# led2ch_v0_2.net
KiCad netlist of a schematic drawn in EAGLE
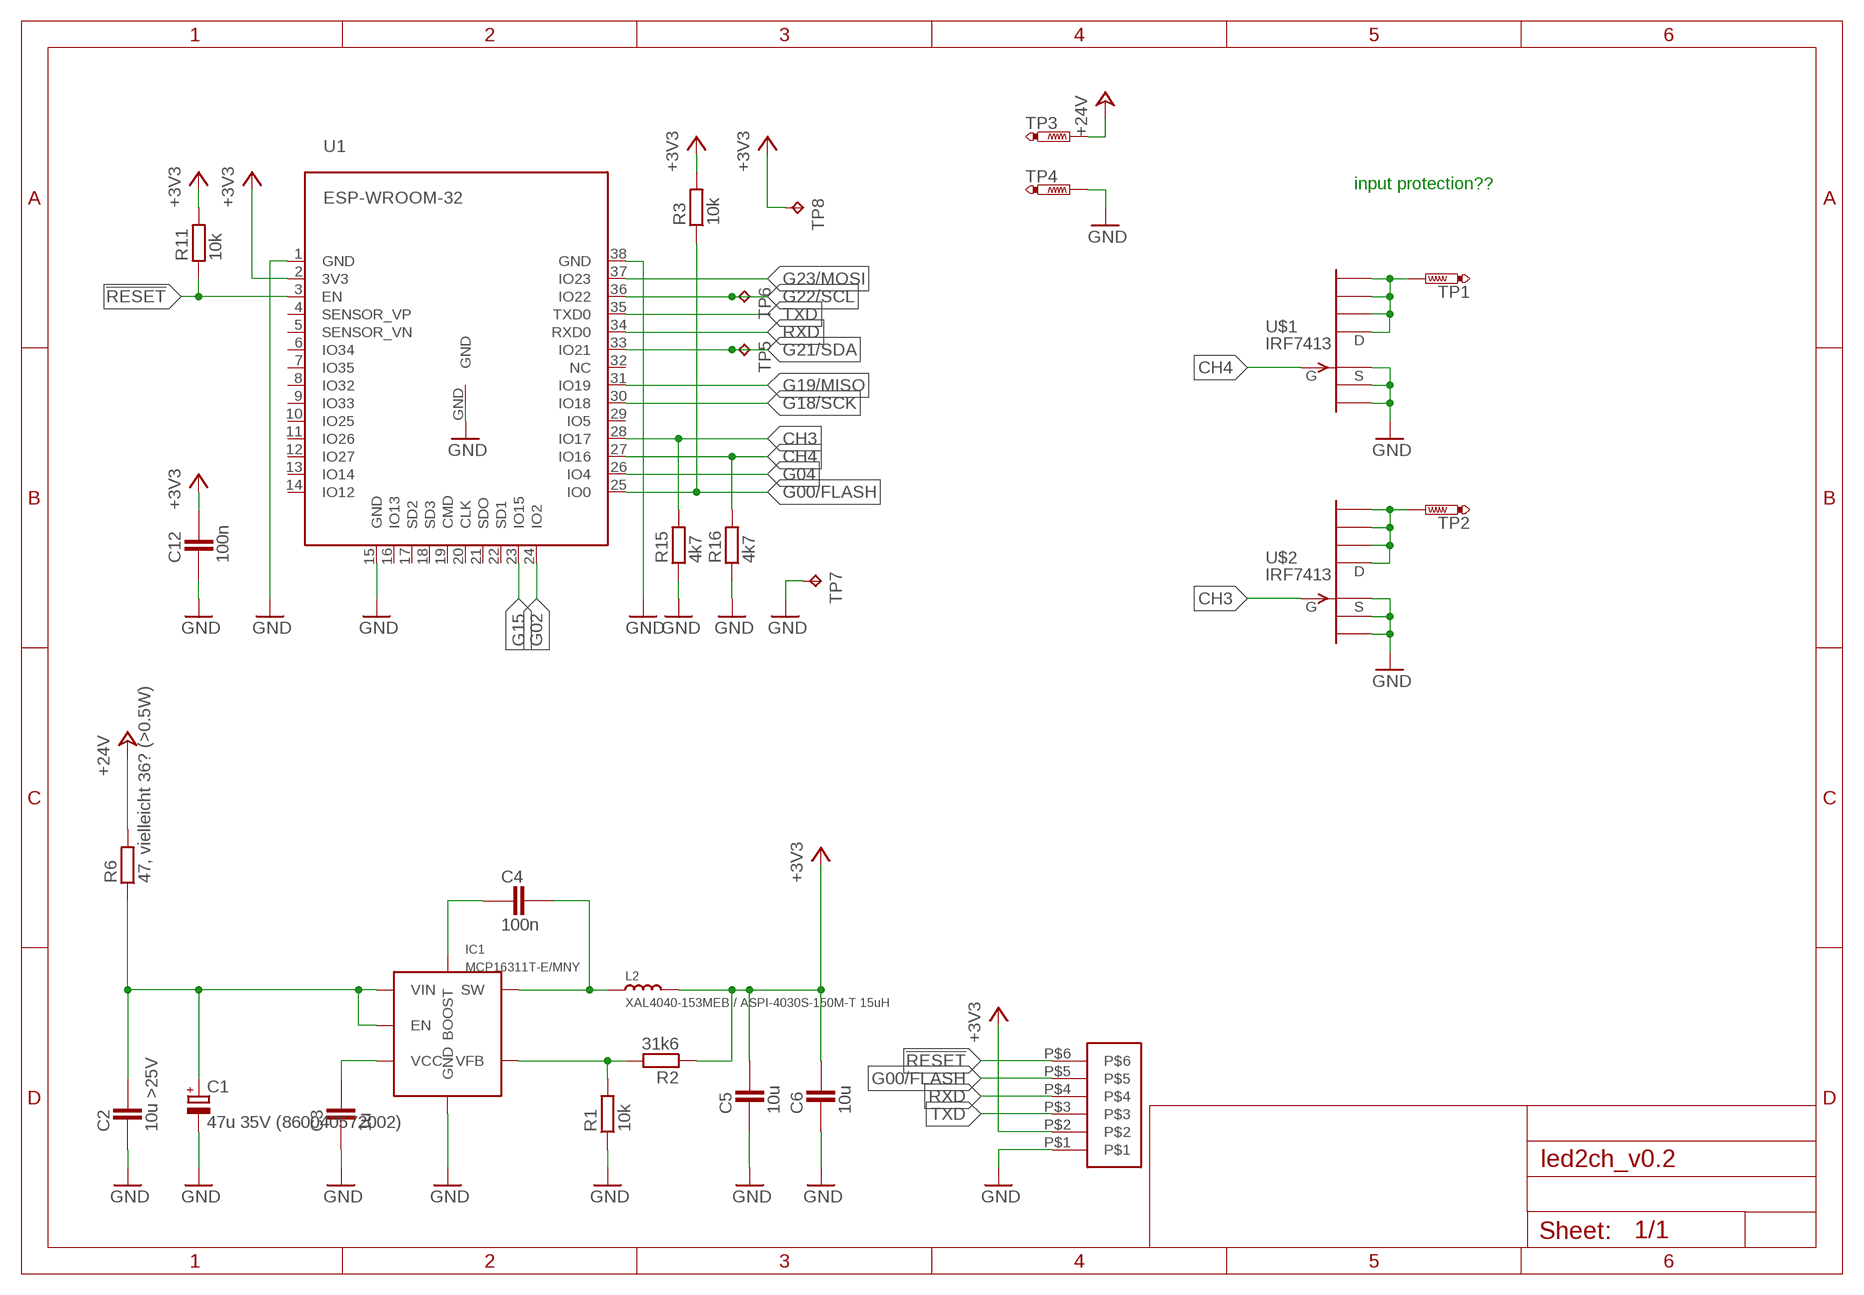
[diagram p0: schematic, sheet 1]

(export (version "E")
  (design (tool "Eeschema 10.0.6"))
  (components
    (comp (ref "C1")
      (value "47u 35V (860040572002)")
      (footprint "eagle-import:E2-5")
      (libsource (lib "eagle-import") (part "CPOL-EUE2-5"))
    )
    (comp (ref "C2")
      (value "10u >25V")
      (footprint "eagle-import:CAPC2012X145AN")
      (libsource (lib "eagle-import") (part "CAPACITOR_0805"))
    )
    (comp (ref "C3")
      (value "1u")
      (footprint "eagle-import:CAPC1608X92N")
      (libsource (lib "eagle-import") (part "CAPACITOR_0603"))
    )
    (comp (ref "C4")
      (value "100n")
      (footprint "eagle-import:CAPC1005X60N")
      (libsource (lib "eagle-import") (part "CAPACITOR_0402"))
    )
    (comp (ref "C5")
      (value "10u")
      (footprint "eagle-import:CAPC2012X145AN")
      (libsource (lib "eagle-import") (part "CAPACITOR_0805"))
    )
    (comp (ref "C6")
      (value "10u")
      (footprint "eagle-import:CAPC2012X145AN")
      (libsource (lib "eagle-import") (part "CAPACITOR_0805"))
    )
    (comp (ref "C12")
      (value "100n")
      (footprint "eagle-import:CAPC1005X60N")
      (libsource (lib "eagle-import") (part "CAPACITOR_0402"))
    )
    (comp (ref "IC1")
      (value "MCP16311T-E/MNY")
      (footprint "eagle-import:TDFN8")
      (libsource (lib "eagle-import") (part "MCP16311-TDFN"))
    )
    (comp (ref "L2")
      (value "XAL4040-153MEB / ASPI-4030S-150M-T 15uH")
      (footprint "eagle-import:L0420")
      (fields (field (name "MPN") "SPD3D16-4R7M"))
      (libsource (lib "eagle-import") (part "SMD-POWER-INDUCTOR-4.7UH-20%-750MA(2P-3.9X3.9MM)"))
    )
    (comp (ref "R1")
      (value "10k")
      (footprint "eagle-import:RESC1005X40AN")
      (libsource (lib "eagle-import") (part "RESISTOR_0402"))
    )
    (comp (ref "R2")
      (value "31k6")
      (footprint "eagle-import:RESC1005X40AN")
      (libsource (lib "eagle-import") (part "RESISTOR_0402"))
    )
    (comp (ref "R3")
      (value "10k")
      (footprint "eagle-import:RESC1005X40AN")
      (libsource (lib "eagle-import") (part "RESISTOR_0402"))
    )
    (comp (ref "R6")
      (value "47, vielleicht 36? (>0.5W)")
      (footprint "eagle-import:RESC3115X70N")
      (libsource (lib "eagle-import") (part "RESISTOR_1206"))
    )
    (comp (ref "R11")
      (value "10k")
      (footprint "eagle-import:RESC1005X40AN")
      (libsource (lib "eagle-import") (part "RESISTOR_0402"))
    )
    (comp (ref "R15")
      (value "4k7")
      (footprint "eagle-import:RESC1005X40AN")
      (libsource (lib "eagle-import") (part "RESISTOR_0402"))
    )
    (comp (ref "R16")
      (value "4k7")
      (footprint "eagle-import:RESC1005X40AN")
      (libsource (lib "eagle-import") (part "RESISTOR_0402"))
    )
    (comp (ref "TP1")
      (value "PTR1B1,27")
      (footprint "eagle-import:B1,27")
      (libsource (lib "eagle-import") (part "PTR1B1,27"))
    )
    (comp (ref "TP2")
      (value "PTR1B1,27")
      (footprint "eagle-import:B1,27")
      (libsource (lib "eagle-import") (part "PTR1B1,27"))
    )
    (comp (ref "TP3")
      (value "PTR1B2,54")
      (footprint "eagle-import:B2,54")
      (libsource (lib "eagle-import") (part "PTR1B2,54"))
    )
    (comp (ref "TP4")
      (value "PTR1B2,54")
      (footprint "eagle-import:B2,54")
      (libsource (lib "eagle-import") (part "PTR1B2,54"))
    )
    (comp (ref "TP5")
      (value "TPB1,27")
      (footprint "eagle-import:B1,27")
      (libsource (lib "eagle-import") (part "TPB1,27"))
    )
    (comp (ref "TP6")
      (value "TPB1,27")
      (footprint "eagle-import:B1,27")
      (libsource (lib "eagle-import") (part "TPB1,27"))
    )
    (comp (ref "TP7")
      (value "TPB1,27")
      (footprint "eagle-import:B1,27")
      (libsource (lib "eagle-import") (part "TPB1,27"))
    )
    (comp (ref "TP8")
      (value "TPB1,27")
      (footprint "eagle-import:B1,27")
      (libsource (lib "eagle-import") (part "TPB1,27"))
    )
    (comp (ref "U$1")
      (value "IRF7413")
      (footprint "eagle-import:SO-8")
      (libsource (lib "eagle-import") (part "IRF7413"))
    )
    (comp (ref "U$2")
      (value "IRF7413")
      (footprint "eagle-import:SO-8")
      (libsource (lib "eagle-import") (part "IRF7413"))
    )
    (comp (ref "U$3")
      (value "3X2-2.00RM")
      (footprint "eagle-import:3X2-2.00RM")
      (libsource (lib "eagle-import") (part "3X2-2.00RM"))
    )
    (comp (ref "U1")
      (value "ESP-WROOM-32")
      (footprint "eagle-import:ESP-WROOM-32")
      (libsource (lib "eagle-import") (part "ESP-WROOM-32"))
    )
  )
  (nets
    (net (code "1") (name "+3V3") (class "Default")
      (node (ref "C12") (pin "2") (pinfunction "2_2") (pintype "passive"))
      (node (ref "C5") (pin "2") (pinfunction "2_2") (pintype "passive"))
      (node (ref "C6") (pin "2") (pinfunction "2_2") (pintype "passive"))
      (node (ref "L2") (pin "2") (pinfunction "2_2") (pintype "passive"))
      (node (ref "R11") (pin "2") (pinfunction "2_2") (pintype "passive"))
      (node (ref "R2") (pin "1") (pinfunction "1_1") (pintype "passive"))
      (node (ref "R3") (pin "2") (pinfunction "2_2") (pintype "passive"))
      (node (ref "TP8") (pin "TP") (pinfunction "TP_TP") (pintype "input"))
      (node (ref "U$3") (pin "P$2") (pinfunction "P$2_P$2") (pintype "bidirectional"))
      (node (ref "U1") (pin "2") (pinfunction "3V3_2") (pintype "bidirectional"))
    )
    (net (code "2") (name "+24V") (class "Default")
      (node (ref "R6") (pin "2") (pinfunction "2_2") (pintype "passive"))
      (node (ref "TP3") (pin "TP") (pinfunction "TP_TP") (pintype "input"))
    )
    (net (code "3") (name "/~{RESET}") (class "Default")
      (node (ref "R11") (pin "1") (pinfunction "1_1") (pintype "passive"))
      (node (ref "U$3") (pin "P$6") (pinfunction "P$6_P$6") (pintype "bidirectional"))
      (node (ref "U1") (pin "3") (pinfunction "EN_3") (pintype "bidirectional"))
    )
    (net (code "4") (name "CH3") (class "Default")
      (node (ref "R15") (pin "2") (pinfunction "2_2") (pintype "passive"))
      (node (ref "U$2") (pin "4") (pinfunction "G_4") (pintype "passive"))
      (node (ref "U1") (pin "28") (pinfunction "IO17_28") (pintype "bidirectional"))
    )
    (net (code "5") (name "CH4") (class "Default")
      (node (ref "R16") (pin "2") (pinfunction "2_2") (pintype "passive"))
      (node (ref "U$1") (pin "4") (pinfunction "G_4") (pintype "passive"))
      (node (ref "U1") (pin "27") (pinfunction "IO16_27") (pintype "bidirectional"))
    )
    (net (code "6") (name "G00{slash}FLASH") (class "Default")
      (node (ref "R3") (pin "1") (pinfunction "1_1") (pintype "passive"))
      (node (ref "U$3") (pin "P$5") (pinfunction "P$5_P$5") (pintype "bidirectional"))
      (node (ref "U1") (pin "25") (pinfunction "IO0_25") (pintype "bidirectional"))
    )
    (net (code "7") (name "G02") (class "Default")
      (node (ref "U1") (pin "24") (pinfunction "IO2_24") (pintype "bidirectional"))
    )
    (net (code "8") (name "G04") (class "Default")
      (node (ref "U1") (pin "26") (pinfunction "IO4_26") (pintype "bidirectional"))
    )
    (net (code "9") (name "G15") (class "Default")
      (node (ref "U1") (pin "23") (pinfunction "IO15_23") (pintype "bidirectional"))
    )
    (net (code "10") (name "G18{slash}SCK") (class "Default")
      (node (ref "U1") (pin "30") (pinfunction "IO18_30") (pintype "bidirectional"))
    )
    (net (code "11") (name "G19{slash}MISO") (class "Default")
      (node (ref "U1") (pin "31") (pinfunction "IO19_31") (pintype "bidirectional"))
    )
    (net (code "12") (name "G21{slash}SDA") (class "Default")
      (node (ref "TP5") (pin "TP") (pinfunction "TP_TP") (pintype "input"))
      (node (ref "U1") (pin "33") (pinfunction "IO21_33") (pintype "bidirectional"))
    )
    (net (code "13") (name "G22{slash}SCL") (class "Default")
      (node (ref "TP6") (pin "TP") (pinfunction "TP_TP") (pintype "input"))
      (node (ref "U1") (pin "36") (pinfunction "IO22_36") (pintype "bidirectional"))
    )
    (net (code "14") (name "G23{slash}MOSI") (class "Default")
      (node (ref "U1") (pin "37") (pinfunction "IO23_37") (pintype "bidirectional"))
    )
    (net (code "15") (name "GND") (class "Default")
      (node (ref "C1") (pin "-") (pinfunction "-_-") (pintype "passive"))
      (node (ref "C12") (pin "1") (pinfunction "1_1") (pintype "passive"))
      (node (ref "C2") (pin "1") (pinfunction "1_1") (pintype "passive"))
      (node (ref "C3") (pin "1") (pinfunction "1_1") (pintype "passive"))
      (node (ref "C5") (pin "1") (pinfunction "1_1") (pintype "passive"))
      (node (ref "C6") (pin "1") (pinfunction "1_1") (pintype "passive"))
      (node (ref "IC1") (pin "P$5") (pinfunction "GND_P$5") (pintype "bidirectional"))
      (node (ref "IC1") (pin "P$8") (pinfunction "GND_P$8") (pintype "bidirectional"))
      (node (ref "IC1") (pin "P$9") (pinfunction "GND_P$9") (pintype "bidirectional"))
      (node (ref "R1") (pin "1") (pinfunction "1_1") (pintype "passive"))
      (node (ref "R15") (pin "1") (pinfunction "1_1") (pintype "passive"))
      (node (ref "R16") (pin "1") (pinfunction "1_1") (pintype "passive"))
      (node (ref "TP4") (pin "TP") (pinfunction "TP_TP") (pintype "input"))
      (node (ref "TP7") (pin "TP") (pinfunction "TP_TP") (pintype "input"))
      (node (ref "U$1") (pin "1") (pinfunction "S_1") (pintype "passive"))
      (node (ref "U$1") (pin "2") (pinfunction "S1_2") (pintype "passive"))
      (node (ref "U$1") (pin "3") (pinfunction "S2_3") (pintype "passive"))
      (node (ref "U$2") (pin "1") (pinfunction "S_1") (pintype "passive"))
      (node (ref "U$2") (pin "2") (pinfunction "S1_2") (pintype "passive"))
      (node (ref "U$2") (pin "3") (pinfunction "S2_3") (pintype "passive"))
      (node (ref "U$3") (pin "P$1") (pinfunction "P$1_P$1") (pintype "bidirectional"))
      (node (ref "U1") (pin "1") (pinfunction "GND_1") (pintype "bidirectional"))
      (node (ref "U1") (pin "15") (pinfunction "GND_15") (pintype "bidirectional"))
      (node (ref "U1") (pin "38") (pinfunction "GND_38") (pintype "bidirectional"))
      (node (ref "U1") (pin "GND") (pinfunction "GND_GND") (pintype "bidirectional"))
    )
    (net (code "16") (name "Net-(IC1-BOOST)") (class "Default")
      (node (ref "C4") (pin "1") (pinfunction "1_1") (pintype "passive"))
      (node (ref "IC1") (pin "P$7") (pinfunction "BOOST_P$7") (pintype "bidirectional"))
    )
    (net (code "17") (name "Net-(IC1-EN)") (class "Default")
      (node (ref "C1") (pin "+") (pinfunction "+_+") (pintype "passive"))
      (node (ref "C2") (pin "2") (pinfunction "2_2") (pintype "passive"))
      (node (ref "IC1") (pin "P$3") (pinfunction "EN_P$3") (pintype "bidirectional"))
      (node (ref "IC1") (pin "P$4") (pinfunction "VIN_P$4") (pintype "bidirectional"))
      (node (ref "R6") (pin "1") (pinfunction "1_1") (pintype "passive"))
    )
    (net (code "18") (name "Net-(IC1-SW)") (class "Default")
      (node (ref "C4") (pin "2") (pinfunction "2_2") (pintype "passive"))
      (node (ref "IC1") (pin "P$6") (pinfunction "SW_P$6") (pintype "bidirectional"))
      (node (ref "L2") (pin "1") (pinfunction "1_1") (pintype "passive"))
    )
    (net (code "19") (name "Net-(IC1-VCC)") (class "Default")
      (node (ref "C3") (pin "2") (pinfunction "2_2") (pintype "passive"))
      (node (ref "IC1") (pin "P$2") (pinfunction "VCC_P$2") (pintype "bidirectional"))
    )
    (net (code "20") (name "Net-(IC1-VFB)") (class "Default")
      (node (ref "IC1") (pin "P$1") (pinfunction "VFB_P$1") (pintype "bidirectional"))
      (node (ref "R1") (pin "2") (pinfunction "2_2") (pintype "passive"))
      (node (ref "R2") (pin "2") (pinfunction "2_2") (pintype "passive"))
    )
    (net (code "21") (name "Net-(U$1-D)") (class "Default")
      (node (ref "TP1") (pin "TP") (pinfunction "TP_TP") (pintype "input"))
      (node (ref "U$1") (pin "5") (pinfunction "D_5") (pintype "passive"))
      (node (ref "U$1") (pin "6") (pinfunction "D1_6") (pintype "passive"))
      (node (ref "U$1") (pin "7") (pinfunction "D2_7") (pintype "passive"))
      (node (ref "U$1") (pin "8") (pinfunction "D3_8") (pintype "passive"))
    )
    (net (code "22") (name "Net-(U$2-D)") (class "Default")
      (node (ref "TP2") (pin "TP") (pinfunction "TP_TP") (pintype "input"))
      (node (ref "U$2") (pin "5") (pinfunction "D_5") (pintype "passive"))
      (node (ref "U$2") (pin "6") (pinfunction "D1_6") (pintype "passive"))
      (node (ref "U$2") (pin "7") (pinfunction "D2_7") (pintype "passive"))
      (node (ref "U$2") (pin "8") (pinfunction "D3_8") (pintype "passive"))
    )
    (net (code "23") (name "RXD") (class "Default")
      (node (ref "U$3") (pin "P$4") (pinfunction "P$4_P$4") (pintype "bidirectional"))
      (node (ref "U1") (pin "34") (pinfunction "RXD0_34") (pintype "bidirectional"))
    )
    (net (code "24") (name "TXD") (class "Default")
      (node (ref "U$3") (pin "P$3") (pinfunction "P$3_P$3") (pintype "bidirectional"))
      (node (ref "U1") (pin "35") (pinfunction "TXD0_35") (pintype "bidirectional"))
    )
    (net (code "25") (name "unconnected-(U1-CLK-Pad20)") (class "Default")
      (node (ref "U1") (pin "20") (pinfunction "CLK_20") (pintype "bidirectional"))
    )
    (net (code "26") (name "unconnected-(U1-CMD-Pad19)") (class "Default")
      (node (ref "U1") (pin "19") (pinfunction "CMD_19") (pintype "bidirectional"))
    )
    (net (code "27") (name "unconnected-(U1-IO5-Pad29)") (class "Default")
      (node (ref "U1") (pin "29") (pinfunction "IO5_29") (pintype "bidirectional"))
    )
    (net (code "28") (name "unconnected-(U1-IO12-Pad14)") (class "Default")
      (node (ref "U1") (pin "14") (pinfunction "IO12_14") (pintype "bidirectional"))
    )
    (net (code "29") (name "unconnected-(U1-IO13-Pad16)") (class "Default")
      (node (ref "U1") (pin "16") (pinfunction "IO13_16") (pintype "bidirectional"))
    )
    (net (code "30") (name "unconnected-(U1-IO14-Pad13)") (class "Default")
      (node (ref "U1") (pin "13") (pinfunction "IO14_13") (pintype "bidirectional"))
    )
    (net (code "31") (name "unconnected-(U1-IO25-Pad10)") (class "Default")
      (node (ref "U1") (pin "10") (pinfunction "IO25_10") (pintype "bidirectional"))
    )
    (net (code "32") (name "unconnected-(U1-IO26-Pad11)") (class "Default")
      (node (ref "U1") (pin "11") (pinfunction "IO26_11") (pintype "bidirectional"))
    )
    (net (code "33") (name "unconnected-(U1-IO27-Pad12)") (class "Default")
      (node (ref "U1") (pin "12") (pinfunction "IO27_12") (pintype "bidirectional"))
    )
    (net (code "34") (name "unconnected-(U1-IO32-Pad8)") (class "Default")
      (node (ref "U1") (pin "8") (pinfunction "IO32_8") (pintype "bidirectional"))
    )
    (net (code "35") (name "unconnected-(U1-IO33-Pad9)") (class "Default")
      (node (ref "U1") (pin "9") (pinfunction "IO33_9") (pintype "bidirectional"))
    )
    (net (code "36") (name "unconnected-(U1-IO34-Pad6)") (class "Default")
      (node (ref "U1") (pin "6") (pinfunction "IO34_6") (pintype "bidirectional"))
    )
    (net (code "37") (name "unconnected-(U1-IO35-Pad7)") (class "Default")
      (node (ref "U1") (pin "7") (pinfunction "IO35_7") (pintype "bidirectional"))
    )
    (net (code "38") (name "unconnected-(U1-NC-Pad32)") (class "Default")
      (node (ref "U1") (pin "32") (pinfunction "NC_32") (pintype "bidirectional"))
    )
    (net (code "39") (name "unconnected-(U1-SD1-Pad22)") (class "Default")
      (node (ref "U1") (pin "22") (pinfunction "SD1_22") (pintype "bidirectional"))
    )
    (net (code "40") (name "unconnected-(U1-SD2-Pad17)") (class "Default")
      (node (ref "U1") (pin "17") (pinfunction "SD2_17") (pintype "bidirectional"))
    )
    (net (code "41") (name "unconnected-(U1-SD3-Pad18)") (class "Default")
      (node (ref "U1") (pin "18") (pinfunction "SD3_18") (pintype "bidirectional"))
    )
    (net (code "42") (name "unconnected-(U1-SDO-Pad21)") (class "Default")
      (node (ref "U1") (pin "21") (pinfunction "SDO_21") (pintype "bidirectional"))
    )
    (net (code "43") (name "unconnected-(U1-SENSOR_VN-Pad5)") (class "Default")
      (node (ref "U1") (pin "5") (pinfunction "SENSOR_VN_5") (pintype "bidirectional"))
    )
    (net (code "44") (name "unconnected-(U1-SENSOR_VP-Pad4)") (class "Default")
      (node (ref "U1") (pin "4") (pinfunction "SENSOR_VP_4") (pintype "bidirectional"))
    )
  )
)
